# switch_blank.net
KiCad netlist of a schematic drawn in Altium Designer
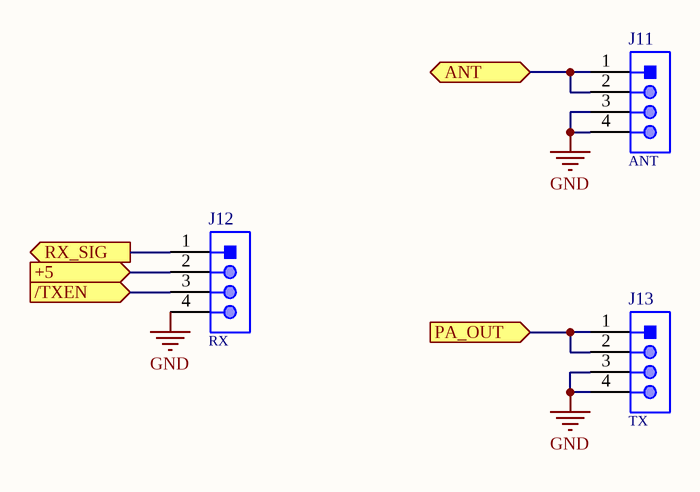
[diagram p0: switch_blank.SchDoc]

(export (version "E")
  (design (tool "Eeschema 10.0.6"))
  (components
    (comp (ref "J11")
      (value "ANT")
      (footprint "61300411121")
      (description "THT Vertical Pin Header WR-PHD, Pitch 2.54 mm, Single Row, 4 pins")
      (fields
        (field (name "MANUFACTURER") "Wurth Elektronik")
        (field (name "PART NUMBER") "61300411121")
        (field (name "PUBLISHER") "WurthElektronik")
      )
      (libsource (lib "Altium Content Vault") (part "WE-CN-1P-M-R4"))
    )
    (comp (ref "J12")
      (value "RX")
      (footprint "61300411121")
      (description "THT Vertical Pin Header WR-PHD, Pitch 2.54 mm, Single Row, 4 pins")
      (fields
        (field (name "MANUFACTURER") "Wurth Elektronik")
        (field (name "PART NUMBER") "61300411121")
        (field (name "PUBLISHER") "WurthElektronik")
      )
      (libsource (lib "Altium Content Vault") (part "WE-CN-1P-M-R4"))
    )
    (comp (ref "J13")
      (value "TX")
      (footprint "61300411121")
      (description "THT Vertical Pin Header WR-PHD, Pitch 2.54 mm, Single Row, 4 pins")
      (fields
        (field (name "MANUFACTURER") "Wurth Elektronik")
        (field (name "PART NUMBER") "61300411121")
        (field (name "PUBLISHER") "WurthElektronik")
      )
      (libsource (lib "Altium Content Vault") (part "WE-CN-1P-M-R4"))
    )
  )
  (nets
    (net (code "1") (name "/+5") (class "Default")
      (node (ref "J12") (pin "2") (pinfunction "2_2") (pintype "passive"))
    )
    (net (code "2") (name "/ANT") (class "Default")
      (node (ref "J11") (pin "1") (pinfunction "1_1") (pintype "passive"))
      (node (ref "J11") (pin "2") (pinfunction "2_2") (pintype "passive"))
    )
    (net (code "3") (name "/PA_OUT") (class "Default")
      (node (ref "J13") (pin "1") (pinfunction "1_1") (pintype "passive"))
      (node (ref "J13") (pin "2") (pinfunction "2_2") (pintype "passive"))
    )
    (net (code "4") (name "/RX_SIG") (class "Default")
      (node (ref "J12") (pin "1") (pinfunction "1_1") (pintype "passive"))
    )
    (net (code "5") (name "/{slash}TXEN") (class "Default")
      (node (ref "J12") (pin "3") (pinfunction "3_3") (pintype "passive"))
    )
    (net (code "6") (name "GND") (class "Default")
      (node (ref "J11") (pin "3") (pinfunction "3_3") (pintype "passive"))
      (node (ref "J11") (pin "4") (pinfunction "4_4") (pintype "passive"))
      (node (ref "J12") (pin "4") (pinfunction "4_4") (pintype "passive"))
      (node (ref "J13") (pin "3") (pinfunction "3_3") (pintype "passive"))
      (node (ref "J13") (pin "4") (pinfunction "4_4") (pintype "passive"))
    )
  )
)
